# Wire.net
KiCad netlist of a schematic drawn in EAGLE
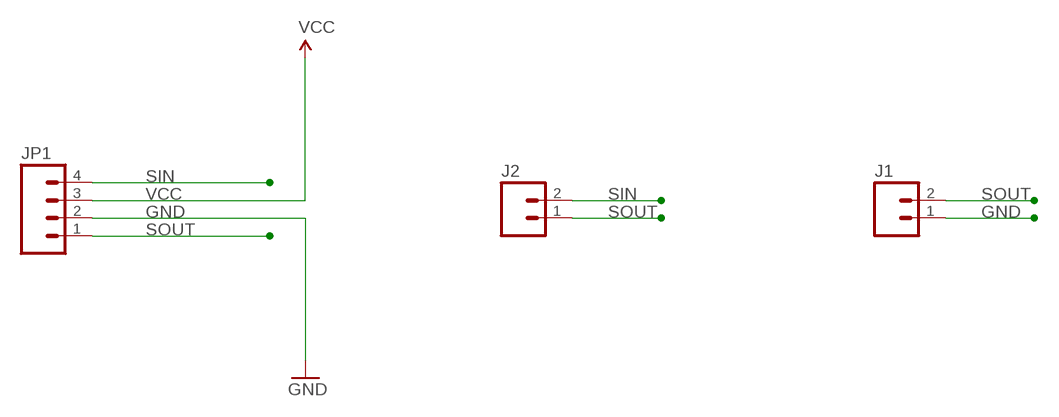
[diagram p0: schematic, sheet 1]

(export (version "E")
  (design (tool "Eeschema 10.0.6"))
  (components
    (comp (ref "J1")
      (value "M02PTH")
      (footprint "eagle-import:1X02")
      (libsource (lib "eagle-import") (part "M02PTH"))
    )
    (comp (ref "J2")
      (value "M02PTH")
      (footprint "eagle-import:1X02")
      (libsource (lib "eagle-import") (part "M02PTH"))
    )
    (comp (ref "JP1")
      (value "M04PTH")
      (footprint "eagle-import:1X04")
      (libsource (lib "eagle-import") (part "M04PTH"))
    )
  )
  (nets
    (net (code "1") (name "/SIN") (class "Default")
      (node (ref "J2") (pin "2") (pinfunction "2_2") (pintype "passive"))
      (node (ref "JP1") (pin "4") (pinfunction "4_4") (pintype "passive"))
    )
    (net (code "2") (name "/SOUT") (class "Default")
      (node (ref "J1") (pin "2") (pinfunction "2_2") (pintype "passive"))
      (node (ref "J2") (pin "1") (pinfunction "1_1") (pintype "passive"))
      (node (ref "JP1") (pin "1") (pinfunction "1_1") (pintype "passive"))
    )
    (net (code "3") (name "GND") (class "Default")
      (node (ref "J1") (pin "1") (pinfunction "1_1") (pintype "passive"))
      (node (ref "JP1") (pin "2") (pinfunction "2_2") (pintype "passive"))
    )
    (net (code "4") (name "VCC") (class "Default")
      (node (ref "JP1") (pin "3") (pinfunction "3_3") (pintype "passive"))
    )
  )
)
